# E17-04-INDUCTIVE_LOAD_SWITCH.net
KiCad netlist of a schematic drawn in Altium Designer
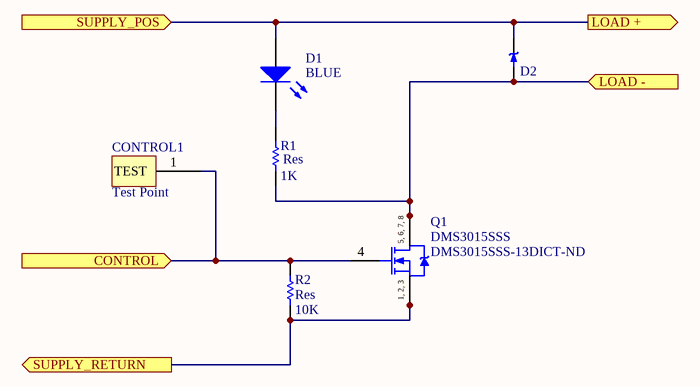
[diagram p0: E17-04-INDUCTIVE_LOAD_SWITCH.SchDoc]

(export (version "E")
  (design (tool "Eeschema 10.0.6"))
  (components
    (comp (ref "CONTROL1")
      (value "Test Point")
      (footprint "TEST POINT 5000K")
      (description "5000-5004, 5015-5019 Keystone Electronics")
      (libsource (lib "Mechanical Devices") (part "Test Point"))
    )
    (comp (ref "D1")
      (value "OVS5MBBCR4")
      (footprint "OVS5MBBCR4")
      (description "Typical BLUE LED")
      (fields (field (name "COLOUR") "BLUE") (field (name "PUBLISHER") "Altium Limited"))
      (libsource (lib "LEDs") (part "OVS5MBBCR4"))
    )
    (comp (ref "D2")
      (value "PMEG4010ET")
      (footprint "SOT23-3")
      (description "SCHOTTKY RECT 40V 1A SOT-23")
      (libsource (lib "Diodes") (part "PMEG4010ET"))
    )
    (comp (ref "Q1")
      (value "DMS3015SSS")
      (footprint "SOIC-8-150")
      (description "N-Channel Power MOSFET")
      (fields (field (name "SUPPLIER PART NUMBER 1") "DMS3015SSS-13DICT-ND"))
      (libsource (lib "Transistors") (part "DMS3015SSS"))
    )
    (comp (ref "R1")
      (value "Res")
      (footprint "2012[0805]")
      (description "Surface Mount Resistor")
      (fields (field (name "ALTIUM_VALUE") "1K") (field (name "PUBLISHER") "Altium Limited"))
      (libsource (lib "Resistors") (part "Res"))
    )
    (comp (ref "R2")
      (value "Res")
      (footprint "2012[0805]")
      (description "Surface Mount Resistor")
      (fields (field (name "ALTIUM_VALUE") "10K") (field (name "PUBLISHER") "Altium Limited"))
      (libsource (lib "Resistors") (part "Res"))
    )
  )
  (nets
    (net (code "1") (name "/CONTROL") (class "Default")
      (node (ref "CONTROL1") (pin "1") (pinfunction "TEST_1") (pintype "passive"))
      (node (ref "Q1") (pin "4") (pinfunction "G_4") (pintype "passive"))
      (node (ref "R2") (pin "2") (pinfunction "2_2") (pintype "passive"))
    )
    (net (code "2") (name "/LOAD +") (class "Default")
      (node (ref "D1") (pin "1") (pinfunction "A_1") (pintype "passive"))
      (node (ref "D2") (pin "3") (pinfunction "3_3") (pintype "passive"))
    )
    (net (code "3") (name "/LOAD -") (class "Default")
      (node (ref "D2") (pin "1") (pinfunction "1_1") (pintype "passive"))
      (node (ref "Q1") (pin "5") (pinfunction "D_5") (pintype "passive"))
      (node (ref "Q1") (pin "6") (pinfunction "D_6") (pintype "passive"))
      (node (ref "Q1") (pin "7") (pinfunction "D_7") (pintype "passive"))
      (node (ref "Q1") (pin "8") (pinfunction "D_8") (pintype "passive"))
      (node (ref "R1") (pin "1") (pinfunction "1_1") (pintype "passive"))
    )
    (net (code "4") (name "/SUPPLY_RETURN") (class "Default")
      (node (ref "Q1") (pin "1") (pinfunction "S_1") (pintype "passive"))
      (node (ref "Q1") (pin "2") (pinfunction "S_2") (pintype "passive"))
      (node (ref "Q1") (pin "3") (pinfunction "S_3") (pintype "passive"))
      (node (ref "R2") (pin "1") (pinfunction "1_1") (pintype "passive"))
    )
    (net (code "5") (name "Net-(D1-K)") (class "Default")
      (node (ref "D1") (pin "2") (pinfunction "K_2") (pintype "passive"))
      (node (ref "R1") (pin "2") (pinfunction "2_2") (pintype "passive"))
    )
  )
)
